# alexakit2.net
KiCad netlist of a schematic drawn in EAGLE
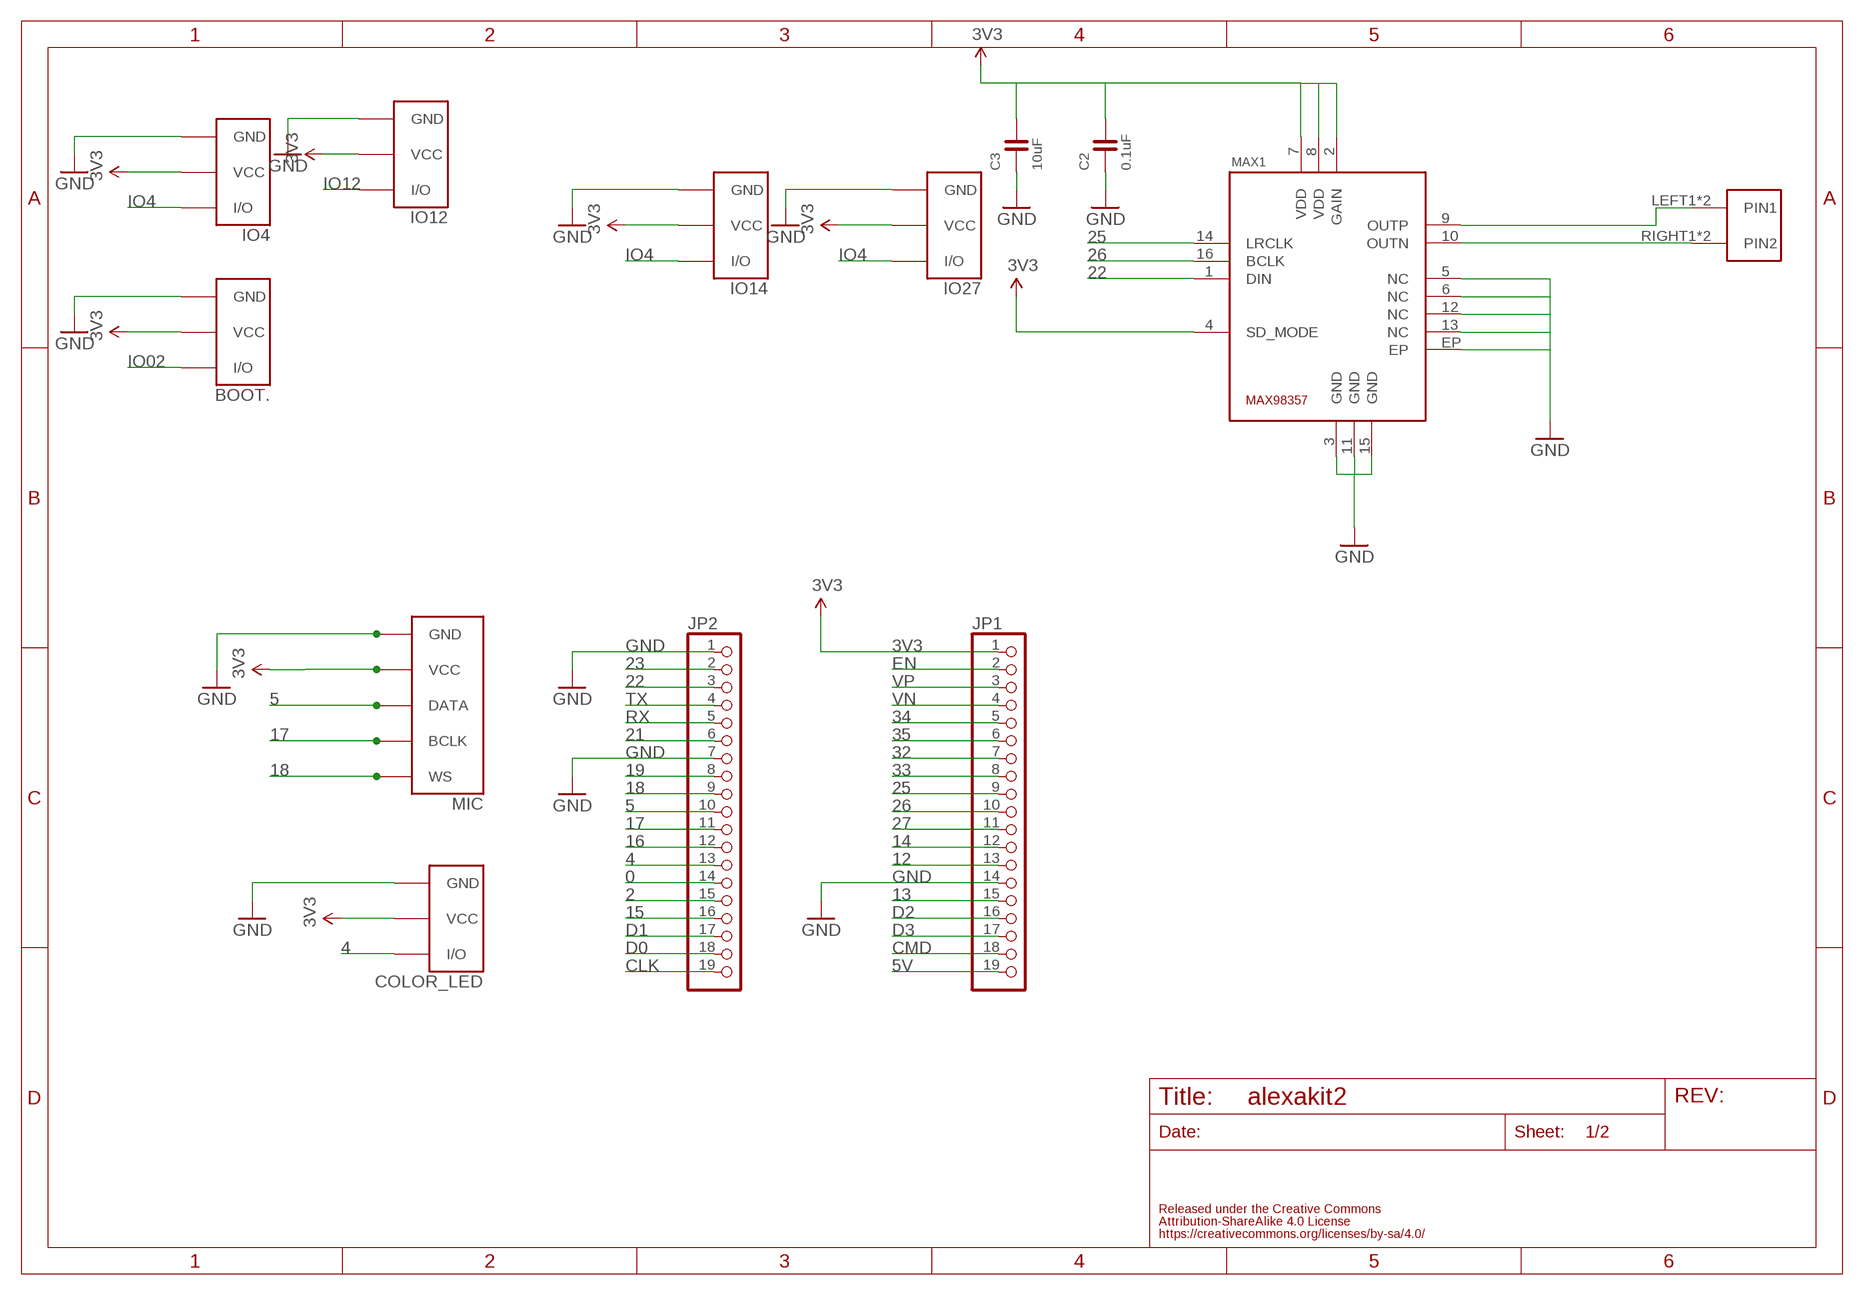
[diagram p0: schematic, sheet 1]
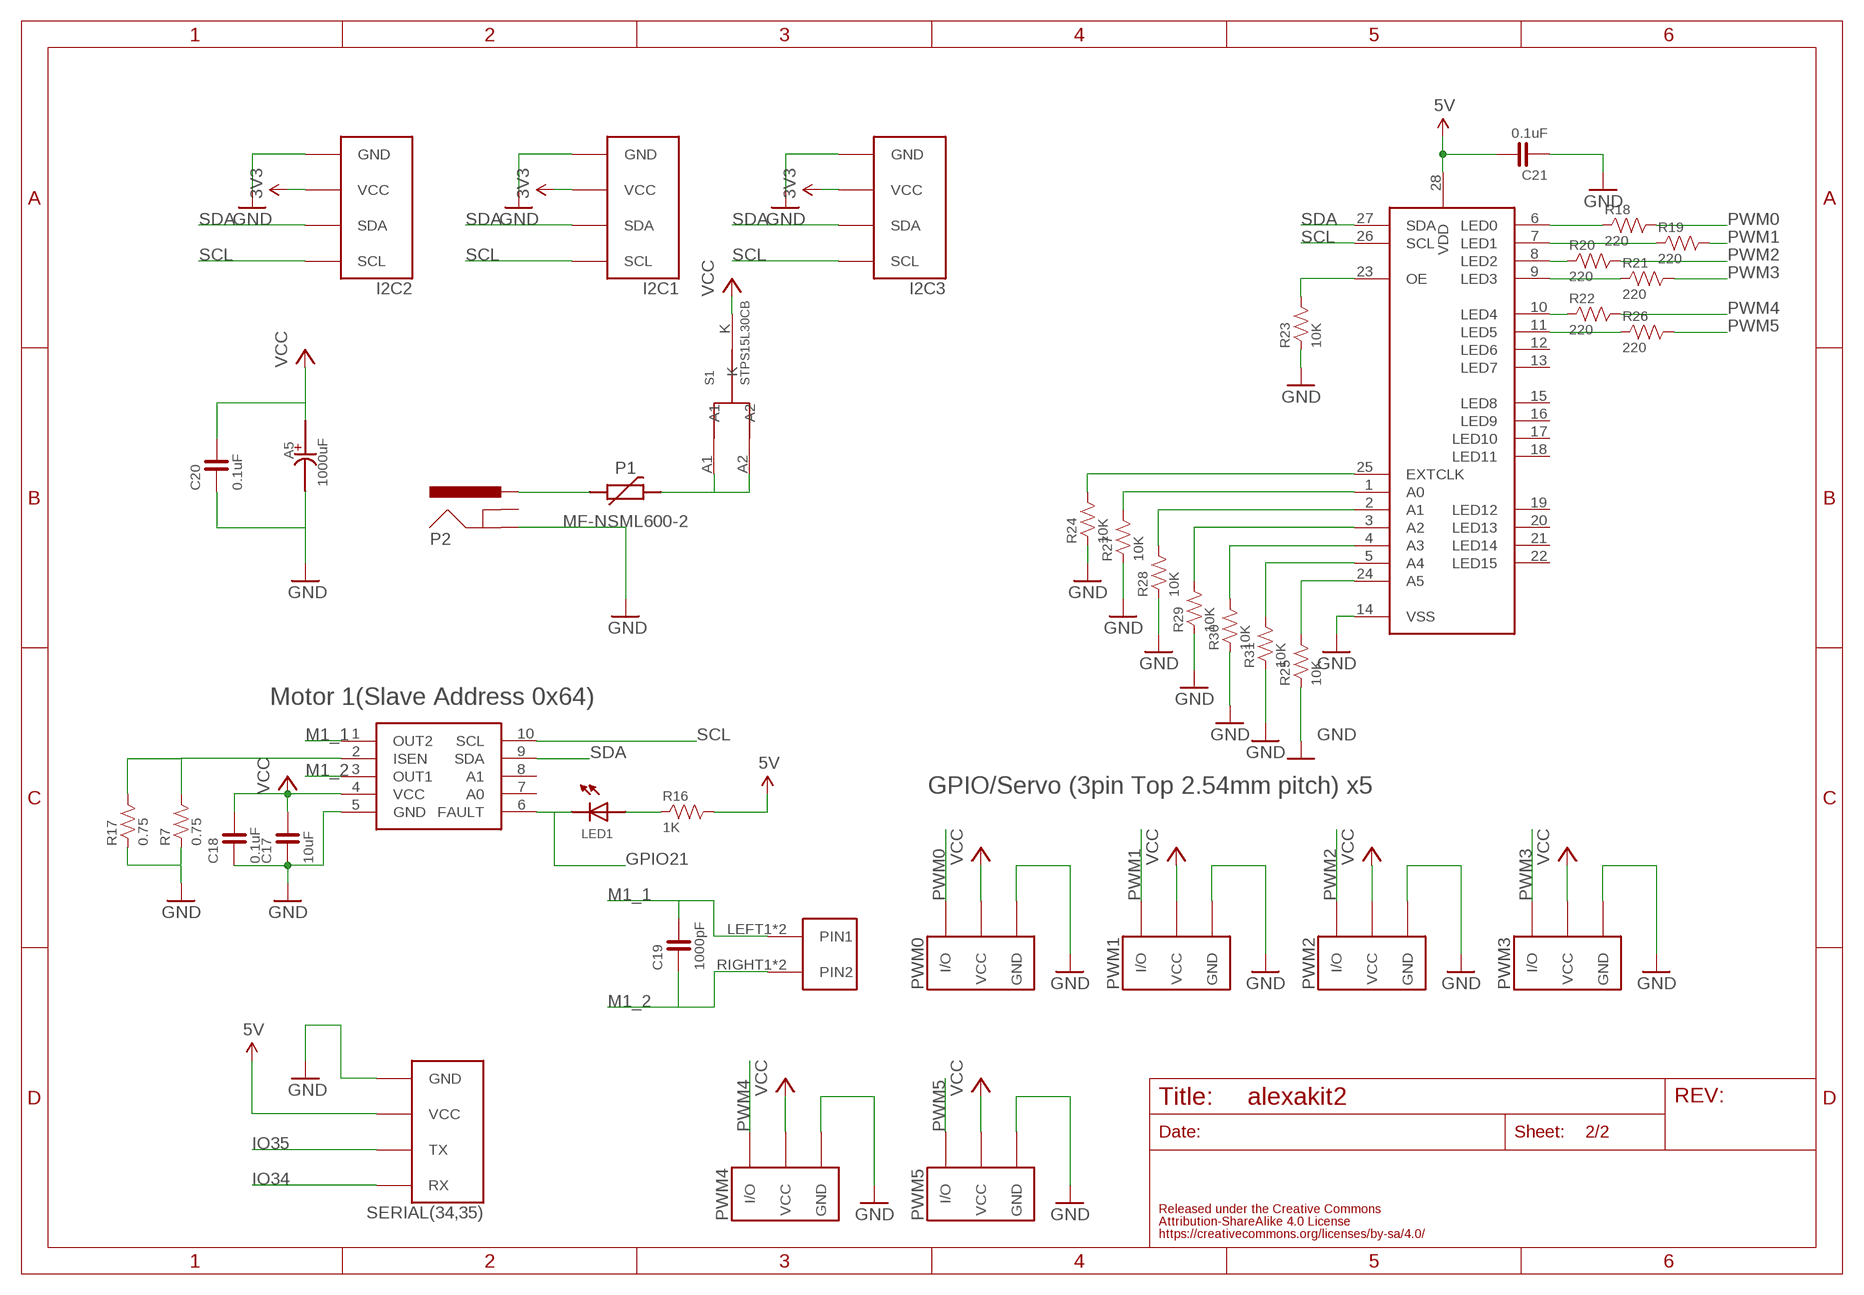
[diagram p1: schematic, sheet 2]

(export (version "E")
  (design (tool "Eeschema 10.0.6"))
  (components
    (comp (ref "BOOT.")
      (value "BUTTON")
      (footprint "eagle-import:FABO_BRICK_3PIN_B03B-PASK-1_NAME_BOTTOM")
      (libsource (lib "eagle-import") (part "FABO_BRICK_3PIN-03B-PASK-1_NAME_BOTTOM"))
    )
    (comp (ref "C2")
      (value "0.1uF")
      (footprint "eagle-import:0603")
      (libsource (lib "eagle-import") (part "CAPACITOR-0603"))
    )
    (comp (ref "C3")
      (value "10uF")
      (footprint "eagle-import:0603")
      (libsource (lib "eagle-import") (part "CAPACITOR-0603"))
    )
    (comp (ref "COLOR_LED")
      (value "FABO_BRICK_3PIN-03B-PASK-1_NAME_BOTTOM")
      (footprint "eagle-import:FABO_BRICK_3PIN_B03B-PASK-1_NAME_BOTTOM")
      (libsource (lib "eagle-import") (part "FABO_BRICK_3PIN-03B-PASK-1_NAME_BOTTOM"))
    )
    (comp (ref "IO4")
      (value "FABO_BRICK_3PIN-03B-PASK-1_NAME_BOTTOM")
      (footprint "eagle-import:FABO_BRICK_3PIN_B03B-PASK-1_NAME_BOTTOM")
      (libsource (lib "eagle-import") (part "FABO_BRICK_3PIN-03B-PASK-1_NAME_BOTTOM"))
    )
    (comp (ref "IO12")
      (value "FABO_BRICK_3PIN-03B-PASK-1_NAME_BOTTOM")
      (footprint "eagle-import:FABO_BRICK_3PIN_B03B-PASK-1_NAME_BOTTOM")
      (libsource (lib "eagle-import") (part "FABO_BRICK_3PIN-03B-PASK-1_NAME_BOTTOM"))
    )
    (comp (ref "IO14")
      (value "FABO_BRICK_3PIN-03B-PASK-1_NAME_BOTTOM")
      (footprint "eagle-import:FABO_BRICK_3PIN_B03B-PASK-1_NAME_BOTTOM")
      (libsource (lib "eagle-import") (part "FABO_BRICK_3PIN-03B-PASK-1_NAME_BOTTOM"))
    )
    (comp (ref "IO27")
      (value "FABO_BRICK_3PIN-03B-PASK-1_NAME_BOTTOM")
      (footprint "eagle-import:FABO_BRICK_3PIN_B03B-PASK-1_NAME_BOTTOM")
      (libsource (lib "eagle-import") (part "FABO_BRICK_3PIN-03B-PASK-1_NAME_BOTTOM"))
    )
    (comp (ref "JP1")
      (value "PINHD-1X19")
      (footprint "eagle-import:1X19")
      (libsource (lib "eagle-import") (part "PINHD-1X19"))
    )
    (comp (ref "JP2")
      (value "PINHD-1X19")
      (footprint "eagle-import:1X19")
      (libsource (lib "eagle-import") (part "PINHD-1X19"))
    )
    (comp (ref "MAX1")
      (value "MA-MAX98357")
      (footprint "eagle-import:MAXIM-MAX98357")
      (libsource (lib "eagle-import") (part "MA-MAX98357"))
    )
    (comp (ref "MIC")
      (value "FABO_BRICK_I2STOP")
      (footprint "eagle-import:FABO_BRICK_I2S_B05B-PARK-1")
      (libsource (lib "eagle-import") (part "FABO_BRICK_I2STOP"))
    )
    (comp (ref "U$4")
      (value "ML-1400-S1")
      (footprint "eagle-import:ML-1400-S1")
      (libsource (lib "eagle-import") (part "ML-1400-S1"))
    )
    (comp (ref "A5")
      (value "1000uF")
      (footprint "eagle-import:D12.5")
      (libsource (lib "eagle-import") (part "CAPACITOR-ALUMIN_D12_5"))
    )
    (comp (ref "C17")
      (value "10uF")
      (footprint "eagle-import:0603")
      (libsource (lib "eagle-import") (part "CAPACITOR-0603"))
    )
    (comp (ref "C18")
      (value "0.1uF")
      (footprint "eagle-import:0603")
      (libsource (lib "eagle-import") (part "CAPACITOR-0603"))
    )
    (comp (ref "C19")
      (value "1000pF")
      (footprint "eagle-import:0603")
      (libsource (lib "eagle-import") (part "CAPACITOR-0603"))
    )
    (comp (ref "C20")
      (value "0.1uF")
      (footprint "eagle-import:0603")
      (libsource (lib "eagle-import") (part "CAPACITOR-0603"))
    )
    (comp (ref "C21")
      (value "0.1uF")
      (footprint "eagle-import:0603")
      (libsource (lib "eagle-import") (part "CAPACITOR-0603"))
    )
    (comp (ref "I2C1")
      (value "FABO_BRICK_I2C-B04B-PASK-1")
      (footprint "eagle-import:FABO_BRICK_I2C_B04B-PASK-1")
      (libsource (lib "eagle-import") (part "FABO_BRICK_I2C-B04B-PASK-1"))
    )
    (comp (ref "I2C2")
      (value "FABO_BRICK_I2C-B04B-PASK-1")
      (footprint "eagle-import:FABO_BRICK_I2C_B04B-PASK-1")
      (libsource (lib "eagle-import") (part "FABO_BRICK_I2C-B04B-PASK-1"))
    )
    (comp (ref "I2C3")
      (value "FABO_BRICK_I2C-B04B-PASK-1")
      (footprint "eagle-import:FABO_BRICK_I2C_B04B-PASK-1")
      (libsource (lib "eagle-import") (part "FABO_BRICK_I2C-B04B-PASK-1"))
    )
    (comp (ref "LED1")
      (value "LED-0603")
      (footprint "eagle-import:0603")
      (libsource (lib "eagle-import") (part "LED-0603"))
    )
    (comp (ref "P1")
      (value "MF-NSML600-2")
      (footprint "eagle-import:1206")
      (libsource (lib "eagle-import") (part "POLYSWITCH1206"))
    )
    (comp (ref "P2")
      (value "DC-JACKM04339A0")
      (footprint "eagle-import:M04339A0")
      (libsource (lib "eagle-import") (part "DC-JACKM04339A0"))
    )
    (comp (ref "PWM0")
      (value "FABO_BRICK_3PIN-HEADER")
      (footprint "eagle-import:FABO_BRICK_3PIN_HEADER")
      (libsource (lib "eagle-import") (part "FABO_BRICK_3PIN-HEADER"))
    )
    (comp (ref "PWM1")
      (value "FABO_BRICK_3PIN-HEADER")
      (footprint "eagle-import:FABO_BRICK_3PIN_HEADER")
      (libsource (lib "eagle-import") (part "FABO_BRICK_3PIN-HEADER"))
    )
    (comp (ref "PWM2")
      (value "FABO_BRICK_3PIN-HEADER")
      (footprint "eagle-import:FABO_BRICK_3PIN_HEADER")
      (libsource (lib "eagle-import") (part "FABO_BRICK_3PIN-HEADER"))
    )
    (comp (ref "PWM3")
      (value "FABO_BRICK_3PIN-HEADER")
      (footprint "eagle-import:FABO_BRICK_3PIN_HEADER")
      (libsource (lib "eagle-import") (part "FABO_BRICK_3PIN-HEADER"))
    )
    (comp (ref "PWM4")
      (value "FABO_BRICK_3PIN-HEADER")
      (footprint "eagle-import:FABO_BRICK_3PIN_HEADER")
      (libsource (lib "eagle-import") (part "FABO_BRICK_3PIN-HEADER"))
    )
    (comp (ref "PWM5")
      (value "FABO_BRICK_3PIN-HEADER")
      (footprint "eagle-import:FABO_BRICK_3PIN_HEADER")
      (libsource (lib "eagle-import") (part "FABO_BRICK_3PIN-HEADER"))
    )
    (comp (ref "R7")
      (value "0.75")
      (footprint "eagle-import:0603")
      (libsource (lib "eagle-import") (part "RESISTOR-0603"))
    )
    (comp (ref "R16")
      (value "1K")
      (footprint "eagle-import:0603")
      (libsource (lib "eagle-import") (part "RESISTOR-0603"))
    )
    (comp (ref "R17")
      (value "0.75")
      (footprint "eagle-import:0603")
      (libsource (lib "eagle-import") (part "RESISTOR-0603"))
    )
    (comp (ref "R18")
      (value "220")
      (footprint "eagle-import:0603")
      (libsource (lib "eagle-import") (part "RESISTOR-0603"))
    )
    (comp (ref "R19")
      (value "220")
      (footprint "eagle-import:0603")
      (libsource (lib "eagle-import") (part "RESISTOR-0603"))
    )
    (comp (ref "R20")
      (value "220")
      (footprint "eagle-import:0603")
      (libsource (lib "eagle-import") (part "RESISTOR-0603"))
    )
    (comp (ref "R21")
      (value "220")
      (footprint "eagle-import:0603")
      (libsource (lib "eagle-import") (part "RESISTOR-0603"))
    )
    (comp (ref "R22")
      (value "220")
      (footprint "eagle-import:0603")
      (libsource (lib "eagle-import") (part "RESISTOR-0603"))
    )
    (comp (ref "R23")
      (value "10K")
      (footprint "eagle-import:0603")
      (libsource (lib "eagle-import") (part "RESISTOR-0603"))
    )
    (comp (ref "R24")
      (value "10K")
      (footprint "eagle-import:0402")
      (libsource (lib "eagle-import") (part "RESISTOR-0402"))
    )
    (comp (ref "R25")
      (value "10K")
      (footprint "eagle-import:0402")
      (libsource (lib "eagle-import") (part "RESISTOR-0402"))
    )
    (comp (ref "R26")
      (value "220")
      (footprint "eagle-import:0603")
      (libsource (lib "eagle-import") (part "RESISTOR-0603"))
    )
    (comp (ref "R27")
      (value "10K")
      (footprint "eagle-import:0603")
      (libsource (lib "eagle-import") (part "RESISTOR-0603"))
    )
    (comp (ref "R28")
      (value "10K")
      (footprint "eagle-import:0603")
      (libsource (lib "eagle-import") (part "RESISTOR-0603"))
    )
    (comp (ref "R29")
      (value "10K")
      (footprint "eagle-import:0603")
      (libsource (lib "eagle-import") (part "RESISTOR-0603"))
    )
    (comp (ref "R30")
      (value "10K")
      (footprint "eagle-import:0603")
      (libsource (lib "eagle-import") (part "RESISTOR-0603"))
    )
    (comp (ref "R31")
      (value "10K")
      (footprint "eagle-import:0603")
      (libsource (lib "eagle-import") (part "RESISTOR-0603"))
    )
    (comp (ref "S1")
      (value "STPS15L30CB")
      (footprint "eagle-import:STPS15L30C")
      (libsource (lib "eagle-import") (part "STPS15L30C"))
    )
    (comp (ref "SERIAL(34,35)")
      (value "FABO_BRICK_SERIAL-B04B-PASK-1")
      (footprint "eagle-import:FABO_BRICK_SERIAL_B04B-PASK-1")
      (libsource (lib "eagle-import") (part "FABO_BRICK_SERIAL-B04B-PASK-1"))
    )
    (comp (ref "U$8")
      (value "DRV8830")
      (footprint "eagle-import:DRV8830")
      (libsource (lib "eagle-import") (part "DRV8830"))
    )
    (comp (ref "U$9")
      (value "PCA9685")
      (footprint "eagle-import:PCA9685")
      (libsource (lib "eagle-import") (part "PCA9685"))
    )
    (comp (ref "U$12")
      (value "ML-1400-S1")
      (footprint "eagle-import:ML-1400-S1")
      (libsource (lib "eagle-import") (part "ML-1400-S1"))
    )
  )
  (nets
    (net (code "1") (name "0") (class "Default")
      (node (ref "JP2") (pin "14") (pinfunction "14_14") (pintype "passive"))
    )
    (net (code "2") (name "2") (class "Default")
      (node (ref "JP2") (pin "15") (pinfunction "15_15") (pintype "passive"))
    )
    (net (code "3") (name "3V3") (class "Default")
      (node (ref "BOOT.") (pin "VCC") (pinfunction "VCC_VCC") (pintype "bidirectional"))
      (node (ref "C2") (pin "2") (pinfunction "2_2") (pintype "passive"))
      (node (ref "C3") (pin "2") (pinfunction "2_2") (pintype "passive"))
      (node (ref "COLOR_LED") (pin "VCC") (pinfunction "VCC_VCC") (pintype "bidirectional"))
      (node (ref "I2C1") (pin "VCC") (pinfunction "VCC_VCC") (pintype "bidirectional"))
      (node (ref "I2C2") (pin "VCC") (pinfunction "VCC_VCC") (pintype "bidirectional"))
      (node (ref "I2C3") (pin "VCC") (pinfunction "VCC_VCC") (pintype "bidirectional"))
      (node (ref "IO12") (pin "VCC") (pinfunction "VCC_VCC") (pintype "bidirectional"))
      (node (ref "IO14") (pin "VCC") (pinfunction "VCC_VCC") (pintype "bidirectional"))
      (node (ref "IO27") (pin "VCC") (pinfunction "VCC_VCC") (pintype "bidirectional"))
      (node (ref "IO4") (pin "VCC") (pinfunction "VCC_VCC") (pintype "bidirectional"))
      (node (ref "JP1") (pin "1") (pinfunction "1_1") (pintype "passive"))
      (node (ref "MAX1") (pin "2") (pinfunction "GAIN_2") (pintype "bidirectional"))
      (node (ref "MAX1") (pin "4") (pinfunction "SD_MODE_4") (pintype "bidirectional"))
      (node (ref "MAX1") (pin "7") (pinfunction "VDD_7") (pintype "bidirectional"))
      (node (ref "MAX1") (pin "8") (pinfunction "VDD_8") (pintype "bidirectional"))
      (node (ref "MIC") (pin "VCC") (pinfunction "VCC_VCC") (pintype "bidirectional"))
    )
    (net (code "4") (name "4") (class "Default")
      (node (ref "COLOR_LED") (pin "I/O") (pinfunction "I/O_I/O") (pintype "bidirectional"))
      (node (ref "JP2") (pin "13") (pinfunction "13_13") (pintype "passive"))
    )
    (net (code "5") (name "5") (class "Default")
      (node (ref "JP2") (pin "10") (pinfunction "10_10") (pintype "passive"))
      (node (ref "MIC") (pin "DATA") (pinfunction "DATA_DATA") (pintype "bidirectional"))
    )
    (net (code "6") (name "5V") (class "Default")
      (node (ref "C21") (pin "2") (pinfunction "2_2") (pintype "passive"))
      (node (ref "JP1") (pin "19") (pinfunction "19_19") (pintype "passive"))
      (node (ref "R16") (pin "2") (pinfunction "2_2") (pintype "bidirectional"))
      (node (ref "SERIAL(34,35)") (pin "VCC") (pinfunction "VCC_VCC") (pintype "bidirectional"))
      (node (ref "U$9") (pin "28") (pinfunction "VDD_28") (pintype "bidirectional"))
    )
    (net (code "7") (name "12") (class "Default")
      (node (ref "JP1") (pin "13") (pinfunction "13_13") (pintype "passive"))
    )
    (net (code "8") (name "13") (class "Default")
      (node (ref "JP1") (pin "15") (pinfunction "15_15") (pintype "passive"))
    )
    (net (code "9") (name "14") (class "Default")
      (node (ref "JP1") (pin "12") (pinfunction "12_12") (pintype "passive"))
    )
    (net (code "10") (name "15") (class "Default")
      (node (ref "JP2") (pin "16") (pinfunction "16_16") (pintype "passive"))
    )
    (net (code "11") (name "16") (class "Default")
      (node (ref "JP2") (pin "12") (pinfunction "12_12") (pintype "passive"))
    )
    (net (code "12") (name "17") (class "Default")
      (node (ref "JP2") (pin "11") (pinfunction "11_11") (pintype "passive"))
      (node (ref "MIC") (pin "BCLK") (pinfunction "BCLK_BCLK") (pintype "bidirectional"))
    )
    (net (code "13") (name "18") (class "Default")
      (node (ref "JP2") (pin "9") (pinfunction "9_9") (pintype "passive"))
      (node (ref "MIC") (pin "WS") (pinfunction "WS_WS") (pintype "bidirectional"))
    )
    (net (code "14") (name "19") (class "Default")
      (node (ref "JP2") (pin "8") (pinfunction "8_8") (pintype "passive"))
    )
    (net (code "15") (name "21") (class "Default")
      (node (ref "JP2") (pin "6") (pinfunction "6_6") (pintype "passive"))
    )
    (net (code "16") (name "22") (class "Default")
      (node (ref "JP2") (pin "3") (pinfunction "3_3") (pintype "passive"))
      (node (ref "MAX1") (pin "1") (pinfunction "DIN_1") (pintype "bidirectional"))
    )
    (net (code "17") (name "23") (class "Default")
      (node (ref "JP2") (pin "2") (pinfunction "2_2") (pintype "passive"))
    )
    (net (code "18") (name "25") (class "Default")
      (node (ref "JP1") (pin "9") (pinfunction "9_9") (pintype "passive"))
      (node (ref "MAX1") (pin "14") (pinfunction "LRCLK_14") (pintype "bidirectional"))
    )
    (net (code "19") (name "26") (class "Default")
      (node (ref "JP1") (pin "10") (pinfunction "10_10") (pintype "passive"))
      (node (ref "MAX1") (pin "16") (pinfunction "BCLK_16") (pintype "bidirectional"))
    )
    (net (code "20") (name "27") (class "Default")
      (node (ref "JP1") (pin "11") (pinfunction "11_11") (pintype "passive"))
    )
    (net (code "21") (name "32") (class "Default")
      (node (ref "JP1") (pin "7") (pinfunction "7_7") (pintype "passive"))
    )
    (net (code "22") (name "33") (class "Default")
      (node (ref "JP1") (pin "8") (pinfunction "8_8") (pintype "passive"))
    )
    (net (code "23") (name "34") (class "Default")
      (node (ref "JP1") (pin "5") (pinfunction "5_5") (pintype "passive"))
    )
    (net (code "24") (name "35") (class "Default")
      (node (ref "JP1") (pin "6") (pinfunction "6_6") (pintype "passive"))
    )
    (net (code "25") (name "CLK") (class "Default")
      (node (ref "JP2") (pin "19") (pinfunction "19_19") (pintype "passive"))
    )
    (net (code "26") (name "CMD") (class "Default")
      (node (ref "JP1") (pin "18") (pinfunction "18_18") (pintype "passive"))
    )
    (net (code "27") (name "D0") (class "Default")
      (node (ref "JP2") (pin "18") (pinfunction "18_18") (pintype "passive"))
    )
    (net (code "28") (name "D1") (class "Default")
      (node (ref "JP2") (pin "17") (pinfunction "17_17") (pintype "passive"))
    )
    (net (code "29") (name "D2") (class "Default")
      (node (ref "JP1") (pin "16") (pinfunction "16_16") (pintype "passive"))
    )
    (net (code "30") (name "D3") (class "Default")
      (node (ref "JP1") (pin "17") (pinfunction "17_17") (pintype "passive"))
    )
    (net (code "31") (name "EN") (class "Default")
      (node (ref "JP1") (pin "2") (pinfunction "2_2") (pintype "passive"))
    )
    (net (code "32") (name "GND") (class "Default")
      (node (ref "A5") (pin "-") (pinfunction "-_-") (pintype "passive"))
      (node (ref "BOOT.") (pin "GND") (pinfunction "GND_GND") (pintype "bidirectional"))
      (node (ref "C17") (pin "1") (pinfunction "1_1") (pintype "passive"))
      (node (ref "C18") (pin "1") (pinfunction "1_1") (pintype "passive"))
      (node (ref "C2") (pin "1") (pinfunction "1_1") (pintype "passive"))
      (node (ref "C20") (pin "1") (pinfunction "1_1") (pintype "passive"))
      (node (ref "C21") (pin "1") (pinfunction "1_1") (pintype "passive"))
      (node (ref "C3") (pin "1") (pinfunction "1_1") (pintype "passive"))
      (node (ref "COLOR_LED") (pin "GND") (pinfunction "GND_GND") (pintype "bidirectional"))
      (node (ref "I2C1") (pin "GND") (pinfunction "GND_GND") (pintype "bidirectional"))
      (node (ref "I2C2") (pin "GND") (pinfunction "GND_GND") (pintype "bidirectional"))
      (node (ref "I2C3") (pin "GND") (pinfunction "GND_GND") (pintype "bidirectional"))
      (node (ref "IO12") (pin "GND") (pinfunction "GND_GND") (pintype "bidirectional"))
      (node (ref "IO14") (pin "GND") (pinfunction "GND_GND") (pintype "bidirectional"))
      (node (ref "IO27") (pin "GND") (pinfunction "GND_GND") (pintype "bidirectional"))
      (node (ref "IO4") (pin "GND") (pinfunction "GND_GND") (pintype "bidirectional"))
      (node (ref "JP1") (pin "14") (pinfunction "14_14") (pintype "passive"))
      (node (ref "JP2") (pin "1") (pinfunction "1_1") (pintype "passive"))
      (node (ref "JP2") (pin "7") (pinfunction "7_7") (pintype "passive"))
      (node (ref "MAX1") (pin "11") (pinfunction "GND_11") (pintype "bidirectional"))
      (node (ref "MAX1") (pin "12") (pinfunction "NC_12") (pintype "bidirectional"))
      (node (ref "MAX1") (pin "13") (pinfunction "NC_13") (pintype "bidirectional"))
      (node (ref "MAX1") (pin "15") (pinfunction "GND_15") (pintype "bidirectional"))
      (node (ref "MAX1") (pin "3") (pinfunction "GND_3") (pintype "bidirectional"))
      (node (ref "MAX1") (pin "5") (pinfunction "NC_5") (pintype "bidirectional"))
      (node (ref "MAX1") (pin "6") (pinfunction "NC_6") (pintype "bidirectional"))
      (node (ref "MAX1") (pin "EP") (pinfunction "EP_EP") (pintype "bidirectional"))
      (node (ref "MIC") (pin "GND") (pinfunction "GND_GND") (pintype "bidirectional"))
      (node (ref "P2") (pin "GND") (pinfunction "GND_GND") (pintype "bidirectional"))
      (node (ref "PWM0") (pin "GND") (pinfunction "GND_GND") (pintype "bidirectional"))
      (node (ref "PWM1") (pin "GND") (pinfunction "GND_GND") (pintype "bidirectional"))
      (node (ref "PWM2") (pin "GND") (pinfunction "GND_GND") (pintype "bidirectional"))
      (node (ref "PWM3") (pin "GND") (pinfunction "GND_GND") (pintype "bidirectional"))
      (node (ref "PWM4") (pin "GND") (pinfunction "GND_GND") (pintype "bidirectional"))
      (node (ref "PWM5") (pin "GND") (pinfunction "GND_GND") (pintype "bidirectional"))
      (node (ref "R17") (pin "1") (pinfunction "1_1") (pintype "bidirectional"))
      (node (ref "R23") (pin "1") (pinfunction "1_1") (pintype "bidirectional"))
      (node (ref "R24") (pin "P$1") (pinfunction "1_P$1") (pintype "bidirectional"))
      (node (ref "R25") (pin "P$1") (pinfunction "1_P$1") (pintype "bidirectional"))
      (node (ref "R27") (pin "1") (pinfunction "1_1") (pintype "bidirectional"))
      (node (ref "R28") (pin "1") (pinfunction "1_1") (pintype "bidirectional"))
      (node (ref "R29") (pin "1") (pinfunction "1_1") (pintype "bidirectional"))
      (node (ref "R30") (pin "1") (pinfunction "1_1") (pintype "bidirectional"))
      (node (ref "R31") (pin "1") (pinfunction "1_1") (pintype "bidirectional"))
      (node (ref "R7") (pin "1") (pinfunction "1_1") (pintype "bidirectional"))
      (node (ref "SERIAL(34,35)") (pin "GND") (pinfunction "GND_GND") (pintype "bidirectional"))
      (node (ref "U$8") (pin "5") (pinfunction "GND_5") (pintype "bidirectional"))
      (node (ref "U$9") (pin "14") (pinfunction "VSS_14") (pintype "bidirectional"))
    )
    (net (code "33") (name "GPIO21") (class "Default")
      (node (ref "LED1") (pin "CATHODE") (pinfunction "CATHODE_CATHODE") (pintype "passive"))
      (node (ref "U$8") (pin "6") (pinfunction "FAULT_6") (pintype "bidirectional"))
    )
    (net (code "34") (name "IO02") (class "Default")
      (node (ref "BOOT.") (pin "I/O") (pinfunction "I/O_I/O") (pintype "bidirectional"))
    )
    (net (code "35") (name "IO4") (class "Default")
      (node (ref "IO14") (pin "I/O") (pinfunction "I/O_I/O") (pintype "bidirectional"))
      (node (ref "IO27") (pin "I/O") (pinfunction "I/O_I/O") (pintype "bidirectional"))
      (node (ref "IO4") (pin "I/O") (pinfunction "I/O_I/O") (pintype "bidirectional"))
    )
    (net (code "36") (name "IO12") (class "Default")
      (node (ref "IO12") (pin "I/O") (pinfunction "I/O_I/O") (pintype "bidirectional"))
    )
    (net (code "37") (name "IO34") (class "Default")
      (node (ref "SERIAL(34,35)") (pin "RX") (pinfunction "RX_RX") (pintype "bidirectional"))
    )
    (net (code "38") (name "IO35") (class "Default")
      (node (ref "SERIAL(34,35)") (pin "TX") (pinfunction "TX_TX") (pintype "bidirectional"))
    )
    (net (code "39") (name "M1_1") (class "Default")
      (node (ref "C19") (pin "2") (pinfunction "2_2") (pintype "passive"))
      (node (ref "U$12") (pin "LEFT1") (pinfunction "PIN1_LEFT1") (pintype "bidirectional"))
      (node (ref "U$12") (pin "LEFT2") (pinfunction "PIN1_LEFT2") (pintype "bidirectional"))
      (node (ref "U$8") (pin "1") (pinfunction "OUT2_1") (pintype "bidirectional"))
    )
    (net (code "40") (name "M1_2") (class "Default")
      (node (ref "C19") (pin "1") (pinfunction "1_1") (pintype "passive"))
      (node (ref "U$12") (pin "RIGHT1") (pinfunction "PIN2_RIGHT1") (pintype "bidirectional"))
      (node (ref "U$12") (pin "RIGHT2") (pinfunction "PIN2_RIGHT2") (pintype "bidirectional"))
      (node (ref "U$8") (pin "3") (pinfunction "OUT1_3") (pintype "bidirectional"))
    )
    (net (code "41") (name "Net-(LED1-PadANODE)") (class "Default")
      (node (ref "LED1") (pin "ANODE") (pinfunction "ANODE_ANODE") (pintype "passive"))
      (node (ref "R16") (pin "1") (pinfunction "1_1") (pintype "bidirectional"))
    )
    (net (code "42") (name "Net-(MAX1-OUTN)") (class "Default")
      (node (ref "MAX1") (pin "10") (pinfunction "OUTN_10") (pintype "bidirectional"))
      (node (ref "U$4") (pin "RIGHT1") (pinfunction "PIN2_RIGHT1") (pintype "bidirectional"))
      (node (ref "U$4") (pin "RIGHT2") (pinfunction "PIN2_RIGHT2") (pintype "bidirectional"))
    )
    (net (code "43") (name "Net-(MAX1-OUTP)") (class "Default")
      (node (ref "MAX1") (pin "9") (pinfunction "OUTP_9") (pintype "bidirectional"))
      (node (ref "U$4") (pin "LEFT1") (pinfunction "PIN1_LEFT1") (pintype "bidirectional"))
      (node (ref "U$4") (pin "LEFT2") (pinfunction "PIN1_LEFT2") (pintype "bidirectional"))
    )
    (net (code "44") (name "Net-(P1-1)") (class "Default")
      (node (ref "P1") (pin "P$1") (pinfunction "1_P$1") (pintype "bidirectional"))
      (node (ref "P2") (pin "VCC") (pinfunction "PWR_VCC") (pintype "bidirectional"))
    )
    (net (code "45") (name "Net-(P1-2)") (class "Default")
      (node (ref "P1") (pin "P$2") (pinfunction "2_P$2") (pintype "bidirectional"))
      (node (ref "S1") (pin "A1") (pinfunction "A1_A1") (pintype "bidirectional"))
      (node (ref "S1") (pin "A2") (pinfunction "A2_A2") (pintype "bidirectional"))
    )
    (net (code "46") (name "Net-(R24-2)") (class "Default")
      (node (ref "R24") (pin "P$2") (pinfunction "2_P$2") (pintype "bidirectional"))
      (node (ref "U$9") (pin "25") (pinfunction "EXTCLK_25") (pintype "bidirectional"))
    )
    (net (code "47") (name "Net-(R25-2)") (class "Default")
      (node (ref "R25") (pin "P$2") (pinfunction "2_P$2") (pintype "bidirectional"))
      (node (ref "U$9") (pin "24") (pinfunction "A5_24") (pintype "bidirectional"))
    )
    (net (code "48") (name "Net-(U$8-ISEN)") (class "Default")
      (node (ref "R17") (pin "2") (pinfunction "2_2") (pintype "bidirectional"))
      (node (ref "R7") (pin "2") (pinfunction "2_2") (pintype "bidirectional"))
      (node (ref "U$8") (pin "2") (pinfunction "ISEN_2") (pintype "bidirectional"))
    )
    (net (code "49") (name "Net-(U$9-A0)") (class "Default")
      (node (ref "R27") (pin "2") (pinfunction "2_2") (pintype "bidirectional"))
      (node (ref "U$9") (pin "1") (pinfunction "A0_1") (pintype "bidirectional"))
    )
    (net (code "50") (name "Net-(U$9-A1)") (class "Default")
      (node (ref "R28") (pin "2") (pinfunction "2_2") (pintype "bidirectional"))
      (node (ref "U$9") (pin "2") (pinfunction "A1_2") (pintype "bidirectional"))
    )
    (net (code "51") (name "Net-(U$9-A2)") (class "Default")
      (node (ref "R29") (pin "2") (pinfunction "2_2") (pintype "bidirectional"))
      (node (ref "U$9") (pin "3") (pinfunction "A2_3") (pintype "bidirectional"))
    )
    (net (code "52") (name "Net-(U$9-A3)") (class "Default")
      (node (ref "R30") (pin "2") (pinfunction "2_2") (pintype "bidirectional"))
      (node (ref "U$9") (pin "4") (pinfunction "A3_4") (pintype "bidirectional"))
    )
    (net (code "53") (name "Net-(U$9-A4)") (class "Default")
      (node (ref "R31") (pin "2") (pinfunction "2_2") (pintype "bidirectional"))
      (node (ref "U$9") (pin "5") (pinfunction "A4_5") (pintype "bidirectional"))
    )
    (net (code "54") (name "Net-(U$9-LED0)") (class "Default")
      (node (ref "R18") (pin "1") (pinfunction "1_1") (pintype "bidirectional"))
      (node (ref "U$9") (pin "6") (pinfunction "LED0_6") (pintype "bidirectional"))
    )
    (net (code "55") (name "Net-(U$9-LED1)") (class "Default")
      (node (ref "R19") (pin "1") (pinfunction "1_1") (pintype "bidirectional"))
      (node (ref "U$9") (pin "7") (pinfunction "LED1_7") (pintype "bidirectional"))
    )
    (net (code "56") (name "Net-(U$9-LED2)") (class "Default")
      (node (ref "R20") (pin "1") (pinfunction "1_1") (pintype "bidirectional"))
      (node (ref "U$9") (pin "8") (pinfunction "LED2_8") (pintype "bidirectional"))
    )
    (net (code "57") (name "Net-(U$9-LED3)") (class "Default")
      (node (ref "R21") (pin "1") (pinfunction "1_1") (pintype "bidirectional"))
      (node (ref "U$9") (pin "9") (pinfunction "LED3_9") (pintype "bidirectional"))
    )
    (net (code "58") (name "Net-(U$9-LED4)") (class "Default")
      (node (ref "R22") (pin "1") (pinfunction "1_1") (pintype "bidirectional"))
      (node (ref "U$9") (pin "10") (pinfunction "LED4_10") (pintype "bidirectional"))
    )
    (net (code "59") (name "Net-(U$9-LED5)") (class "Default")
      (node (ref "R26") (pin "1") (pinfunction "1_1") (pintype "bidirectional"))
      (node (ref "U$9") (pin "11") (pinfunction "LED5_11") (pintype "bidirectional"))
    )
    (net (code "60") (name "Net-(U$9-OE)") (class "Default")
      (node (ref "R23") (pin "2") (pinfunction "2_2") (pintype "bidirectional"))
      (node (ref "U$9") (pin "23") (pinfunction "OE_23") (pintype "bidirectional"))
    )
    (net (code "61") (name "PWM0") (class "Default")
      (node (ref "PWM0") (pin "I/O") (pinfunction "I/O_I/O") (pintype "bidirectional"))
      (node (ref "R18") (pin "2") (pinfunction "2_2") (pintype "bidirectional"))
    )
    (net (code "62") (name "PWM1") (class "Default")
      (node (ref "PWM1") (pin "I/O") (pinfunction "I/O_I/O") (pintype "bidirectional"))
      (node (ref "R19") (pin "2") (pinfunction "2_2") (pintype "bidirectional"))
    )
    (net (code "63") (name "PWM2") (class "Default")
      (node (ref "PWM2") (pin "I/O") (pinfunction "I/O_I/O") (pintype "bidirectional"))
      (node (ref "R20") (pin "2") (pinfunction "2_2") (pintype "bidirectional"))
    )
    (net (code "64") (name "PWM3") (class "Default")
      (node (ref "PWM3") (pin "I/O") (pinfunction "I/O_I/O") (pintype "bidirectional"))
      (node (ref "R21") (pin "2") (pinfunction "2_2") (pintype "bidirectional"))
    )
    (net (code "65") (name "PWM4") (class "Default")
      (node (ref "PWM4") (pin "I/O") (pinfunction "I/O_I/O") (pintype "bidirectional"))
      (node (ref "R22") (pin "2") (pinfunction "2_2") (pintype "bidirectional"))
    )
    (net (code "66") (name "PWM5") (class "Default")
      (node (ref "PWM5") (pin "I/O") (pinfunction "I/O_I/O") (pintype "bidirectional"))
      (node (ref "R26") (pin "2") (pinfunction "2_2") (pintype "bidirectional"))
    )
    (net (code "67") (name "RX") (class "Default")
      (node (ref "JP2") (pin "5") (pinfunction "5_5") (pintype "passive"))
    )
    (net (code "68") (name "SCL") (class "Default")
      (node (ref "I2C1") (pin "SCL") (pinfunction "SCL_SCL") (pintype "bidirectional"))
      (node (ref "I2C2") (pin "SCL") (pinfunction "SCL_SCL") (pintype "bidirectional"))
      (node (ref "I2C3") (pin "SCL") (pinfunction "SCL_SCL") (pintype "bidirectional"))
      (node (ref "U$8") (pin "10") (pinfunction "SCL_10") (pintype "bidirectional"))
      (node (ref "U$9") (pin "26") (pinfunction "SCL_26") (pintype "bidirectional"))
    )
    (net (code "69") (name "SDA") (class "Default")
      (node (ref "I2C1") (pin "SDA") (pinfunction "SDA_SDA") (pintype "bidirectional"))
      (node (ref "I2C2") (pin "SDA") (pinfunction "SDA_SDA") (pintype "bidirectional"))
      (node (ref "I2C3") (pin "SDA") (pinfunction "SDA_SDA") (pintype "bidirectional"))
      (node (ref "U$8") (pin "9") (pinfunction "SDA_9") (pintype "bidirectional"))
      (node (ref "U$9") (pin "27") (pinfunction "SDA_27") (pintype "bidirectional"))
    )
    (net (code "70") (name "TX") (class "Default")
      (node (ref "JP2") (pin "4") (pinfunction "4_4") (pintype "passive"))
    )
    (net (code "71") (name "VCC") (class "Default")
      (node (ref "A5") (pin "+") (pinfunction "+_+") (pintype "passive"))
      (node (ref "C17") (pin "2") (pinfunction "2_2") (pintype "passive"))
      (node (ref "C18") (pin "2") (pinfunction "2_2") (pintype "passive"))
      (node (ref "C20") (pin "2") (pinfunction "2_2") (pintype "passive"))
      (node (ref "PWM0") (pin "VCC") (pinfunction "VCC_VCC") (pintype "bidirectional"))
      (node (ref "PWM1") (pin "VCC") (pinfunction "VCC_VCC") (pintype "bidirectional"))
      (node (ref "PWM2") (pin "VCC") (pinfunction "VCC_VCC") (pintype "bidirectional"))
      (node (ref "PWM3") (pin "VCC") (pinfunction "VCC_VCC") (pintype "bidirectional"))
      (node (ref "PWM4") (pin "VCC") (pinfunction "VCC_VCC") (pintype "bidirectional"))
      (node (ref "PWM5") (pin "VCC") (pinfunction "VCC_VCC") (pintype "bidirectional"))
      (node (ref "S1") (pin "K") (pinfunction "K_K") (pintype "bidirectional"))
      (node (ref "U$8") (pin "4") (pinfunction "VCC_4") (pintype "bidirectional"))
    )
    (net (code "72") (name "VN") (class "Default")
      (node (ref "JP1") (pin "4") (pinfunction "4_4") (pintype "passive"))
    )
    (net (code "73") (name "VP") (class "Default")
      (node (ref "JP1") (pin "3") (pinfunction "3_3") (pintype "passive"))
    )
    (net (code "74") (name "unconnected-(P2-PadGNDBREAK)") (class "Default")
      (node (ref "P2") (pin "GNDBREAK") (pinfunction "GNDBREAK_GNDBREAK") (pintype "bidirectional"))
    )
    (net (code "75") (name "unconnected-(U$8-A0-Pad7)") (class "Default")
      (node (ref "U$8") (pin "7") (pinfunction "A0_7") (pintype "bidirectional"))
    )
    (net (code "76") (name "unconnected-(U$8-A1-Pad8)") (class "Default")
      (node (ref "U$8") (pin "8") (pinfunction "A1_8") (pintype "bidirectional"))
    )
    (net (code "77") (name "unconnected-(U$9-LED6-Pad12)") (class "Default")
      (node (ref "U$9") (pin "12") (pinfunction "LED6_12") (pintype "bidirectional"))
    )
    (net (code "78") (name "unconnected-(U$9-LED7-Pad13)") (class "Default")
      (node (ref "U$9") (pin "13") (pinfunction "LED7_13") (pintype "bidirectional"))
    )
    (net (code "79") (name "unconnected-(U$9-LED8-Pad15)") (class "Default")
      (node (ref "U$9") (pin "15") (pinfunction "LED8_15") (pintype "bidirectional"))
    )
    (net (code "80") (name "unconnected-(U$9-LED9-Pad16)") (class "Default")
      (node (ref "U$9") (pin "16") (pinfunction "LED9_16") (pintype "bidirectional"))
    )
    (net (code "81") (name "unconnected-(U$9-LED10-Pad17)") (class "Default")
      (node (ref "U$9") (pin "17") (pinfunction "LED10_17") (pintype "bidirectional"))
    )
    (net (code "82") (name "unconnected-(U$9-LED11-Pad18)") (class "Default")
      (node (ref "U$9") (pin "18") (pinfunction "LED11_18") (pintype "bidirectional"))
    )
    (net (code "83") (name "unconnected-(U$9-LED12-Pad19)") (class "Default")
      (node (ref "U$9") (pin "19") (pinfunction "LED12_19") (pintype "bidirectional"))
    )
    (net (code "84") (name "unconnected-(U$9-LED13-Pad20)") (class "Default")
      (node (ref "U$9") (pin "20") (pinfunction "LED13_20") (pintype "bidirectional"))
    )
    (net (code "85") (name "unconnected-(U$9-LED14-Pad21)") (class "Default")
      (node (ref "U$9") (pin "21") (pinfunction "LED14_21") (pintype "bidirectional"))
    )
    (net (code "86") (name "unconnected-(U$9-LED15-Pad22)") (class "Default")
      (node (ref "U$9") (pin "22") (pinfunction "LED15_22") (pintype "bidirectional"))
    )
  )
)
